# Harvester.net
KiCad netlist of a schematic drawn in Altium Designer
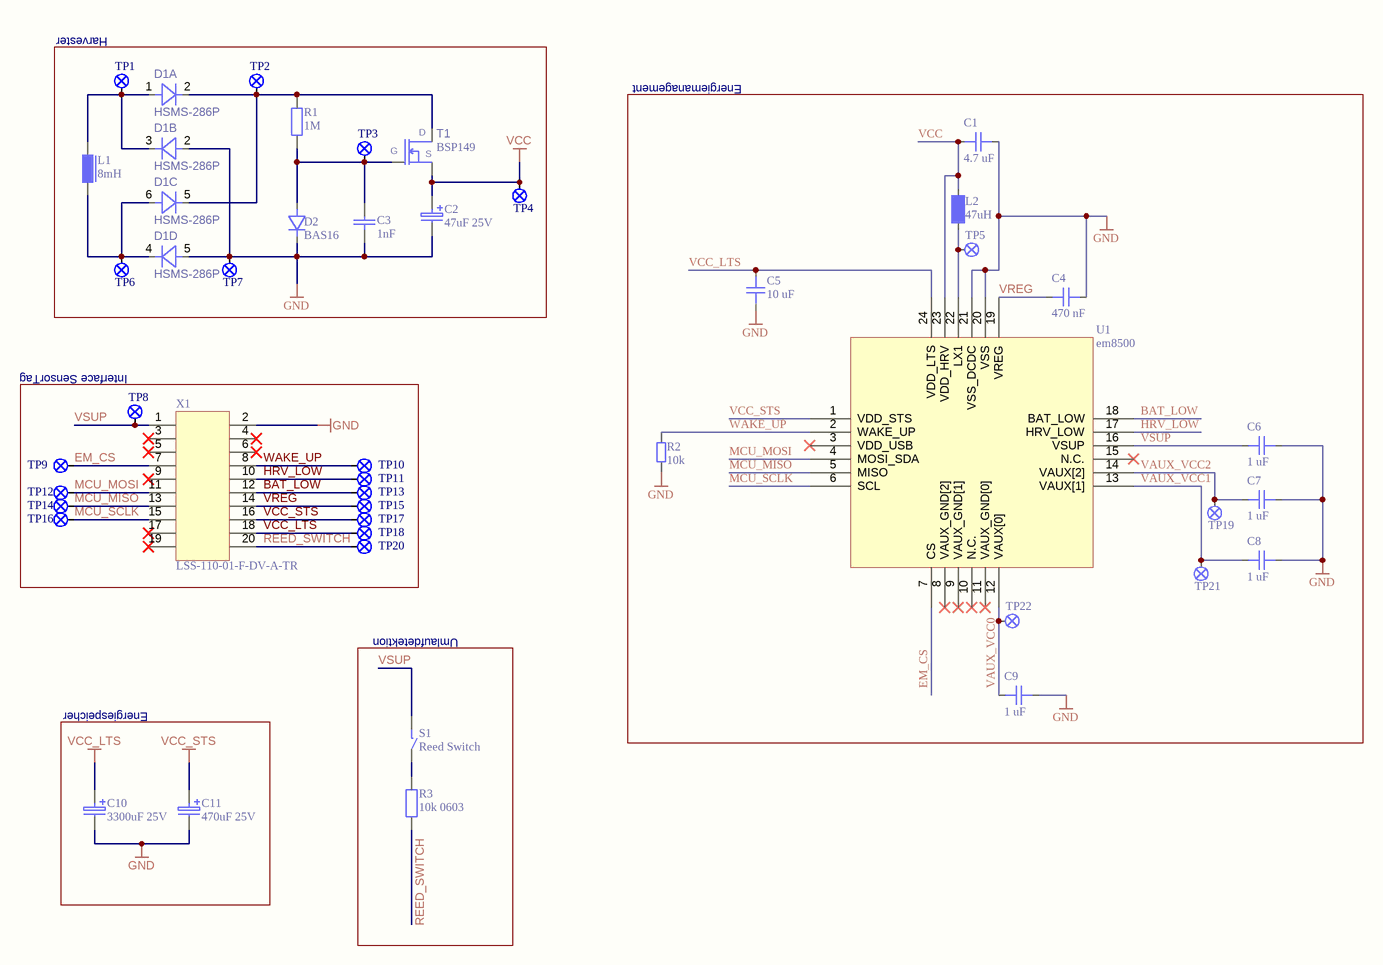
[diagram p0: Harvester.SchDoc]

(export (version "E")
  (design (tool "Eeschema 10.0.6"))
  (components
    (comp (ref "C1")
      (value "4.7 uF")
      (footprint "CHIP 1206")
      (description "Capacitor")
      (fields
        (field (name "MANUFACTURER PART NUMBER") "GRM31CR71E475KA88L")
        (field (name "MANUFACTURER") "Murata")
      )
      (libsource (lib "newlib") (part "C"))
    )
    (comp (ref "C2")
      (value "47uF 25V")
      (footprint "ELKO SMD-C 6.3x6.3")
      (description "Capasitor Polarisiert")
      (fields (field (name "MANUFACTURER") "Vishay"))
      (libsource (lib "60 Passiv") (part "C POL"))
    )
    (comp (ref "C3")
      (value "1nF")
      (footprint "CHIP 0603")
      (description "Capacitor 50V")
      (fields (field (name "MANUFACTURER") "AVX"))
      (libsource (lib "60 Passiv") (part "C 50V"))
    )
    (comp (ref "C4")
      (value "470 nF")
      (footprint "CHIP 0603")
      (description "Capacitor")
      (fields
        (field (name "MANUFACTURER PART NUMBER") "CGA3E3X7R1E474K080AB")
        (field (name "MANUFACTURER") "TDK")
      )
      (libsource (lib "newlib") (part "C"))
    )
    (comp (ref "C5")
      (value "10 uF")
      (footprint "CHIP 1206")
      (description "Capacitor")
      (fields
        (field (name "MANUFACTURER PART NUMBER") "CGA5L1X7R1E106K160AC")
        (field (name "MANUFACTURER") "TDK")
      )
      (libsource (lib "newlib") (part "C"))
    )
    (comp (ref "C6")
      (value "1 uF")
      (footprint "CHIP 0603")
      (description "Capacitor")
      (fields
        (field (name "MANUFACTURER PART NUMBER") "CGA3E1X7R1E105K080AC")
        (field (name "MANUFACTURER") "TDK")
      )
      (libsource (lib "newlib") (part "C"))
    )
    (comp (ref "C7")
      (value "1 uF")
      (footprint "CHIP 0603")
      (description "Capacitor")
      (fields
        (field (name "MANUFACTURER PART NUMBER") "CGA3E1X7R1E105K080AC")
        (field (name "MANUFACTURER") "TDK")
      )
      (libsource (lib "newlib") (part "C"))
    )
    (comp (ref "C8")
      (value "1 uF")
      (footprint "CHIP 0603")
      (description "Capacitor")
      (fields
        (field (name "MANUFACTURER PART NUMBER") "CGA3E1X7R1E105K080AC")
        (field (name "MANUFACTURER") "TDK")
      )
      (libsource (lib "newlib") (part "C"))
    )
    (comp (ref "C9")
      (value "1 uF")
      (footprint "CHIP 0603")
      (description "Capacitor")
      (fields
        (field (name "MANUFACTURER PART NUMBER") "CGA3E1X7R1E105K080AC")
        (field (name "MANUFACTURER") "TDK")
      )
      (libsource (lib "newlib") (part "C"))
    )
    (comp (ref "C10")
      (value "3300uF 25V")
      (footprint "C_RAD_flex")
      (description "Capasitor Polarisiert")
      (fields (field (name "MANUFACTURER") "Panasonic"))
      (libsource (lib "60 Passiv") (part "C POL"))
    )
    (comp (ref "C11")
      (value "470uF 25V")
      (footprint "C_RAD_flex")
      (description "Capasitor Polarisiert")
      (fields (field (name "MANUFACTURER") "Panasonic"))
      (libsource (lib "60 Passiv") (part "C POL"))
    )
    (comp (ref "D1")
      (value "HSMS-286P")
      (footprint "SOT-363 (SC-70)")
      (description "Diode Schottky Quadro")
      (fields (field (name "MANUFACTURER") "Avago"))
      (libsource (lib "10 Halbleiter Passiv") (part "HSMS-286P"))
    )
    (comp (ref "D2")
      (value "BAS16")
      (footprint "Standard:SOT-23")
      (description "Diode")
      (fields (field (name "MANUFACTURER") "ON SEMICONDUCTOR"))
      (libsource (lib "10 Halbleiter Passiv") (part "D"))
    )
    (comp (ref "L1")
      (value "8mH")
      (footprint "WE_74458308")
      (description "Inductor")
      (fields (field (name "MANUFACTURER") "Würth Elektronik"))
      (libsource (lib "60 Passiv") (part "L"))
    )
    (comp (ref "L2")
      (value "47uH")
      (footprint "CHIP 0805")
      (description "Ind")
      (fields
        (field (name "MANUFACTURER PART NUMBER") "0805PS-473KLB")
        (field (name "MANUFACTURER") "Coilcraft")
      )
      (libsource (lib "newlib") (part "L"))
    )
    (comp (ref "R1")
      (value "1M")
      (footprint "CHIP 0603")
      (description "Resistor")
      (fields (field (name "MANUFACTURER") "Vishay"))
      (libsource (lib "60 Passiv") (part "R"))
    )
    (comp (ref "R2")
      (value "10k")
      (footprint "CHIP 0603")
      (description "Resistor")
      (fields
        (field (name "MANUFACTURER PART NUMBER") "CRCW06031K00FKEA")
        (field (name "MANUFACTURER") "Vishay")
      )
      (libsource (lib "newlib") (part "R"))
    )
    (comp (ref "R3")
      (value "10k 0603")
      (footprint "CHIP 0603")
      (description "Resistor")
      (fields (field (name "MANUFACTURER") "Vishay"))
      (libsource (lib "60 Passiv") (part "R"))
    )
    (comp (ref "S1")
      (value "Reed Switch")
      (footprint "MK16-C-2")
      (description "Switch Micro Normal Open")
      (fields (field (name "MANUFACTURER") "STANDEXMEDER"))
      (libsource (lib "80 Stecker & Mech") (part "SWITCH MICRO NO"))
    )
    (comp (ref "T1")
      (value "BSP149")
      (footprint "SOT-223")
      (description "MOSFET N-Kanal")
      (fields (field (name "MANUFACTURER") "Infineon"))
      (libsource (lib "20 Halbleiter Analog") (part "BSP149"))
    )
    (comp (ref "TP1")
      (value "TP_SMD")
      (footprint "TP SMD")
      (description "Testpoint SMD")
      (libsource (lib "80 Stecker & Mech") (part "TP_SMD"))
    )
    (comp (ref "TP2")
      (value "TP_SMD")
      (footprint "TP SMD")
      (description "Testpoint SMD")
      (libsource (lib "80 Stecker & Mech") (part "TP_SMD"))
    )
    (comp (ref "TP3")
      (value "TP_SMD")
      (footprint "TP SMD")
      (description "Testpoint SMD")
      (libsource (lib "80 Stecker & Mech") (part "TP_SMD"))
    )
    (comp (ref "TP4")
      (value "TP_SMD")
      (footprint "TP SMD")
      (description "Testpoint SMD")
      (libsource (lib "80 Stecker & Mech") (part "TP_SMD"))
    )
    (comp (ref "TP5")
      (value "TP_SMD")
      (footprint "TP SMD")
      (description "Testpoint SMD")
      (libsource (lib "80 Stecker & Mech") (part "TP_SMD"))
    )
    (comp (ref "TP6")
      (value "TP_SMD")
      (footprint "TP SMD")
      (description "Testpoint SMD")
      (libsource (lib "80 Stecker & Mech") (part "TP_SMD"))
    )
    (comp (ref "TP7")
      (value "TP_SMD")
      (footprint "TP SMD")
      (description "Testpoint SMD")
      (libsource (lib "80 Stecker & Mech") (part "TP_SMD"))
    )
    (comp (ref "TP8")
      (value "TP_SMD")
      (footprint "TP SMD")
      (description "Testpoint SMD")
      (libsource (lib "80 Stecker & Mech") (part "TP_SMD"))
    )
    (comp (ref "TP9")
      (value "TP_SMD")
      (footprint "TP SMD")
      (description "Testpoint SMD")
      (libsource (lib "80 Stecker & Mech") (part "TP_SMD"))
    )
    (comp (ref "TP10")
      (value "TP_SMD")
      (footprint "TP SMD")
      (description "Testpoint SMD")
      (libsource (lib "80 Stecker & Mech") (part "TP_SMD"))
    )
    (comp (ref "TP11")
      (value "TP_SMD")
      (footprint "TP SMD")
      (description "Testpoint SMD")
      (libsource (lib "80 Stecker & Mech") (part "TP_SMD"))
    )
    (comp (ref "TP12")
      (value "TP_SMD")
      (footprint "TP SMD")
      (description "Testpoint SMD")
      (libsource (lib "80 Stecker & Mech") (part "TP_SMD"))
    )
    (comp (ref "TP13")
      (value "TP_SMD")
      (footprint "TP SMD")
      (description "Testpoint SMD")
      (libsource (lib "80 Stecker & Mech") (part "TP_SMD"))
    )
    (comp (ref "TP14")
      (value "TP_SMD")
      (footprint "TP SMD")
      (description "Testpoint SMD")
      (libsource (lib "80 Stecker & Mech") (part "TP_SMD"))
    )
    (comp (ref "TP15")
      (value "TP_SMD")
      (footprint "TP SMD")
      (description "Testpoint SMD")
      (libsource (lib "80 Stecker & Mech") (part "TP_SMD"))
    )
    (comp (ref "TP16")
      (value "TP_SMD")
      (footprint "TP SMD")
      (description "Testpoint SMD")
      (libsource (lib "80 Stecker & Mech") (part "TP_SMD"))
    )
    (comp (ref "TP17")
      (value "TP_SMD")
      (footprint "TP SMD")
      (description "Testpoint SMD")
      (libsource (lib "80 Stecker & Mech") (part "TP_SMD"))
    )
    (comp (ref "TP18")
      (value "TP_SMD")
      (footprint "TP SMD")
      (description "Testpoint SMD")
      (libsource (lib "80 Stecker & Mech") (part "TP_SMD"))
    )
    (comp (ref "TP19")
      (value "TP_SMD")
      (footprint "TP SMD")
      (description "Testpoint SMD")
      (libsource (lib "80 Stecker & Mech") (part "TP_SMD"))
    )
    (comp (ref "TP20")
      (value "TP_SMD")
      (footprint "TP SMD")
      (description "Testpoint SMD")
      (libsource (lib "80 Stecker & Mech") (part "TP_SMD"))
    )
    (comp (ref "TP21")
      (value "TP_SMD")
      (footprint "TP SMD")
      (description "Testpoint SMD")
      (libsource (lib "80 Stecker & Mech") (part "TP_SMD"))
    )
    (comp (ref "TP22")
      (value "TP_SMD")
      (footprint "TP SMD")
      (description "Testpoint SMD")
      (libsource (lib "80 Stecker & Mech") (part "TP_SMD"))
    )
    (comp (ref "U1")
      (value "em8500")
      (footprint "QFN-24")
      (fields
        (field (name "MANUFACTURER") "EM Microelectronic")
        (field (name "MANUFACTURER PART NUMBER") "EM8500")
      )
      (libsource (lib "Schlib1") (part "em8500"))
    )
    (comp (ref "X1")
      (value "LSS-110-01-F-DV-A-TR")
      (footprint "HEADER SMD 2x10 0.635mm")
      (description "Header 100 mil 20 Pol")
      (fields (field (name "MANUFACTURER") "Samtech"))
      (libsource (lib "80 Stecker & Mech") (part "HDR 20 POL ABW"))
    )
  )
  (nets
    (net (code "1") (name "/BAT_LOW") (class "Default")
      (node (ref "TP13") (pin "1") (pinfunction "1_1") (pintype "passive"))
      (node (ref "U1") (pin "18") (pinfunction "BAT_LOW_18") (pintype "passive"))
      (node (ref "X1") (pin "12") (pinfunction "12_12") (pintype "passive"))
    )
    (net (code "2") (name "/EM_CS") (class "Default")
      (node (ref "TP9") (pin "1") (pinfunction "1_1") (pintype "passive"))
      (node (ref "U1") (pin "7") (pinfunction "CS_7") (pintype "passive"))
      (node (ref "X1") (pin "7") (pinfunction "7_7") (pintype "passive"))
    )
    (net (code "3") (name "/HRV_LOW") (class "Default")
      (node (ref "TP11") (pin "1") (pinfunction "1_1") (pintype "passive"))
      (node (ref "U1") (pin "17") (pinfunction "HRV_LOW_17") (pintype "passive"))
      (node (ref "X1") (pin "10") (pinfunction "10_10") (pintype "passive"))
    )
    (net (code "4") (name "/MCU_MISO") (class "Default")
      (node (ref "TP14") (pin "1") (pinfunction "1_1") (pintype "passive"))
      (node (ref "U1") (pin "5") (pinfunction "MISO_5") (pintype "passive"))
      (node (ref "X1") (pin "13") (pinfunction "13_13") (pintype "passive"))
    )
    (net (code "5") (name "/MCU_MOSI") (class "Default")
      (node (ref "TP12") (pin "1") (pinfunction "1_1") (pintype "passive"))
      (node (ref "U1") (pin "4") (pinfunction "MOSI_SDA_4") (pintype "passive"))
      (node (ref "X1") (pin "11") (pinfunction "11_11") (pintype "passive"))
    )
    (net (code "6") (name "/MCU_SCLK") (class "Default")
      (node (ref "TP16") (pin "1") (pinfunction "1_1") (pintype "passive"))
      (node (ref "U1") (pin "6") (pinfunction "SCL_6") (pintype "passive"))
      (node (ref "X1") (pin "15") (pinfunction "15_15") (pintype "passive"))
    )
    (net (code "7") (name "/REED_SWITCH") (class "Default")
      (node (ref "R3") (pin "1") (pinfunction "1_1") (pintype "passive"))
      (node (ref "TP20") (pin "1") (pinfunction "1_1") (pintype "passive"))
      (node (ref "X1") (pin "20") (pinfunction "20_20") (pintype "passive"))
    )
    (net (code "8") (name "/VAUX_VCC0") (class "Default")
      (node (ref "C9") (pin "1") (pinfunction "1_1") (pintype "passive"))
      (node (ref "TP22") (pin "1") (pinfunction "1_1") (pintype "passive"))
      (node (ref "U1") (pin "12") (pinfunction "VAUX[0]_12") (pintype "passive"))
    )
    (net (code "9") (name "/VAUX_VCC1") (class "Default")
      (node (ref "C8") (pin "1") (pinfunction "1_1") (pintype "passive"))
      (node (ref "TP21") (pin "1") (pinfunction "1_1") (pintype "passive"))
      (node (ref "U1") (pin "13") (pinfunction "VAUX[1]_13") (pintype "passive"))
    )
    (net (code "10") (name "/VAUX_VCC2") (class "Default")
      (node (ref "C7") (pin "1") (pinfunction "1_1") (pintype "passive"))
      (node (ref "TP19") (pin "1") (pinfunction "1_1") (pintype "passive"))
      (node (ref "U1") (pin "14") (pinfunction "VAUX[2]_14") (pintype "passive"))
    )
    (net (code "11") (name "/VREG") (class "Default")
      (node (ref "C4") (pin "1") (pinfunction "1_1") (pintype "passive"))
      (node (ref "TP15") (pin "1") (pinfunction "1_1") (pintype "passive"))
      (node (ref "U1") (pin "19") (pinfunction "VREG_19") (pintype "passive"))
      (node (ref "X1") (pin "14") (pinfunction "14_14") (pintype "passive"))
    )
    (net (code "12") (name "/VSUP") (class "Default")
      (node (ref "C6") (pin "1") (pinfunction "1_1") (pintype "passive"))
      (node (ref "S1") (pin "2") (pinfunction "2_2") (pintype "passive"))
      (node (ref "TP8") (pin "1") (pinfunction "1_1") (pintype "passive"))
      (node (ref "U1") (pin "16") (pinfunction "VSUP_16") (pintype "passive"))
      (node (ref "X1") (pin "1") (pinfunction "1_1") (pintype "passive"))
    )
    (net (code "13") (name "/WAKE_UP") (class "Default")
      (node (ref "R2") (pin "1") (pinfunction "1_1") (pintype "passive"))
      (node (ref "TP10") (pin "1") (pinfunction "1_1") (pintype "passive"))
      (node (ref "U1") (pin "2") (pinfunction "WAKE_UP_2") (pintype "passive"))
      (node (ref "X1") (pin "8") (pinfunction "8_8") (pintype "passive"))
    )
    (net (code "14") (name "GND") (class "Default")
      (node (ref "C1") (pin "2") (pinfunction "2_2") (pintype "passive"))
      (node (ref "C10") (pin "2") (pinfunction "NEG_2") (pintype "passive"))
      (node (ref "C11") (pin "2") (pinfunction "NEG_2") (pintype "passive"))
      (node (ref "C2") (pin "2") (pinfunction "NEG_2") (pintype "passive"))
      (node (ref "C3") (pin "1") (pinfunction "1_1") (pintype "passive"))
      (node (ref "C4") (pin "2") (pinfunction "2_2") (pintype "passive"))
      (node (ref "C5") (pin "2") (pinfunction "2_2") (pintype "passive"))
      (node (ref "C6") (pin "2") (pinfunction "2_2") (pintype "passive"))
      (node (ref "C7") (pin "2") (pinfunction "2_2") (pintype "passive"))
      (node (ref "C8") (pin "2") (pinfunction "2_2") (pintype "passive"))
      (node (ref "C9") (pin "2") (pinfunction "2_2") (pintype "passive"))
      (node (ref "D1") (pin "2") (pinfunction "A_2") (pintype "passive"))
      (node (ref "D1") (pin "5") (pinfunction "A_5") (pintype "passive"))
      (node (ref "D2") (pin "2") (pinfunction "K_2") (pintype "passive"))
      (node (ref "R2") (pin "2") (pinfunction "2_2") (pintype "passive"))
      (node (ref "TP7") (pin "1") (pinfunction "1_1") (pintype "passive"))
      (node (ref "U1") (pin "20") (pinfunction "VSS_20") (pintype "passive"))
      (node (ref "U1") (pin "21") (pinfunction "VSS_DCDC_21") (pintype "passive"))
      (node (ref "X1") (pin "2") (pinfunction "2_2") (pintype "passive"))
    )
    (net (code "15") (name "Net-(D1A-A)") (class "Default")
      (node (ref "D1") (pin "1") (pinfunction "A_1") (pintype "passive"))
      (node (ref "D1") (pin "3") (pinfunction "K_3") (pintype "passive"))
      (node (ref "L1") (pin "2") (pinfunction "2_2") (pintype "passive"))
      (node (ref "TP1") (pin "1") (pinfunction "1_1") (pintype "passive"))
    )
    (net (code "16") (name "Net-(D1A-K)") (class "Default")
      (node (ref "D1") (pin "2") (pinfunction "K_2") (pintype "passive"))
      (node (ref "D1") (pin "5") (pinfunction "K_5") (pintype "passive"))
      (node (ref "R1") (pin "2") (pinfunction "2_2") (pintype "passive"))
      (node (ref "T1") (pin "3") (pinfunction "D_3") (pintype "passive"))
      (node (ref "TP2") (pin "1") (pinfunction "1_1") (pintype "passive"))
    )
    (net (code "17") (name "Net-(D1C-A)") (class "Default")
      (node (ref "D1") (pin "4") (pinfunction "K_4") (pintype "passive"))
      (node (ref "D1") (pin "6") (pinfunction "A_6") (pintype "passive"))
      (node (ref "L1") (pin "1") (pinfunction "1_1") (pintype "passive"))
      (node (ref "TP6") (pin "1") (pinfunction "1_1") (pintype "passive"))
    )
    (net (code "18") (name "Net-(D2-A)") (class "Default")
      (node (ref "C3") (pin "2") (pinfunction "2_2") (pintype "passive"))
      (node (ref "D2") (pin "1") (pinfunction "A_1") (pintype "passive"))
      (node (ref "R1") (pin "1") (pinfunction "1_1") (pintype "passive"))
      (node (ref "T1") (pin "1") (pinfunction "G_1") (pintype "passive"))
      (node (ref "TP3") (pin "1") (pinfunction "1_1") (pintype "passive"))
    )
    (net (code "19") (name "Net-(R3-Pad2)") (class "Default")
      (node (ref "R3") (pin "2") (pinfunction "2_2") (pintype "passive"))
      (node (ref "S1") (pin "1") (pinfunction "1_1") (pintype "passive"))
    )
    (net (code "20") (name "Net-(U1-LX1)") (class "Default")
      (node (ref "L2") (pin "1") (pinfunction "1_1") (pintype "passive"))
      (node (ref "TP5") (pin "1") (pinfunction "1_1") (pintype "passive"))
      (node (ref "U1") (pin "22") (pinfunction "LX1_22") (pintype "passive"))
    )
    (net (code "21") (name "VCC") (class "Default")
      (node (ref "C1") (pin "1") (pinfunction "1_1") (pintype "passive"))
      (node (ref "C2") (pin "1") (pinfunction "POS_1") (pintype "passive"))
      (node (ref "L2") (pin "2") (pinfunction "2_2") (pintype "passive"))
      (node (ref "T1") (pin "2") (pinfunction "S_2") (pintype "passive"))
      (node (ref "TP4") (pin "1") (pinfunction "1_1") (pintype "passive"))
      (node (ref "U1") (pin "23") (pinfunction "VDD_HRV_23") (pintype "passive"))
    )
    (net (code "22") (name "VCC_LTS") (class "Default")
      (node (ref "C10") (pin "1") (pinfunction "POS_1") (pintype "passive"))
      (node (ref "C5") (pin "1") (pinfunction "1_1") (pintype "passive"))
      (node (ref "TP18") (pin "1") (pinfunction "1_1") (pintype "passive"))
      (node (ref "U1") (pin "24") (pinfunction "VDD_LTS_24") (pintype "passive"))
      (node (ref "X1") (pin "18") (pinfunction "18_18") (pintype "passive"))
    )
    (net (code "23") (name "VCC_STS") (class "Default")
      (node (ref "C11") (pin "1") (pinfunction "POS_1") (pintype "passive"))
      (node (ref "TP17") (pin "1") (pinfunction "1_1") (pintype "passive"))
      (node (ref "U1") (pin "1") (pinfunction "VDD_STS_1") (pintype "passive"))
      (node (ref "X1") (pin "16") (pinfunction "16_16") (pintype "passive"))
    )
    (net (code "24") (name "unconnected-(U1-N.C.-Pad10)") (class "Default")
      (node (ref "U1") (pin "10") (pinfunction "N.C._10") (pintype "passive+no_connect"))
    )
    (net (code "25") (name "unconnected-(U1-N.C.-Pad15)") (class "Default")
      (node (ref "U1") (pin "15") (pinfunction "N.C._15") (pintype "passive+no_connect"))
    )
    (net (code "26") (name "unconnected-(U1-VAUX_GND[0]-Pad11)") (class "Default")
      (node (ref "U1") (pin "11") (pinfunction "VAUX_GND[0]_11") (pintype "passive+no_connect"))
    )
    (net (code "27") (name "unconnected-(U1-VAUX_GND[1]-Pad9)") (class "Default")
      (node (ref "U1") (pin "9") (pinfunction "VAUX_GND[1]_9") (pintype "passive+no_connect"))
    )
    (net (code "28") (name "unconnected-(U1-VAUX_GND[2]-Pad8)") (class "Default")
      (node (ref "U1") (pin "8") (pinfunction "VAUX_GND[2]_8") (pintype "passive+no_connect"))
    )
    (net (code "29") (name "unconnected-(U1-VDD_USB-Pad3)") (class "Default")
      (node (ref "U1") (pin "3") (pinfunction "VDD_USB_3") (pintype "passive+no_connect"))
    )
    (net (code "30") (name "unconnected-(X1-Pad3)") (class "Default")
      (node (ref "X1") (pin "3") (pinfunction "3_3") (pintype "passive+no_connect"))
    )
    (net (code "31") (name "unconnected-(X1-Pad4)") (class "Default")
      (node (ref "X1") (pin "4") (pinfunction "4_4") (pintype "passive+no_connect"))
    )
    (net (code "32") (name "unconnected-(X1-Pad5)") (class "Default")
      (node (ref "X1") (pin "5") (pinfunction "5_5") (pintype "passive+no_connect"))
    )
    (net (code "33") (name "unconnected-(X1-Pad6)") (class "Default")
      (node (ref "X1") (pin "6") (pinfunction "6_6") (pintype "passive+no_connect"))
    )
    (net (code "34") (name "unconnected-(X1-Pad9)") (class "Default")
      (node (ref "X1") (pin "9") (pinfunction "9_9") (pintype "passive+no_connect"))
    )
    (net (code "35") (name "unconnected-(X1-Pad17)") (class "Default")
      (node (ref "X1") (pin "17") (pinfunction "17_17") (pintype "passive+no_connect"))
    )
    (net (code "36") (name "unconnected-(X1-Pad19)") (class "Default")
      (node (ref "X1") (pin "19") (pinfunction "19_19") (pintype "passive+no_connect"))
    )
  )
)
